# BusPirate-ultra-testboard_v1_0.net
KiCad netlist of a schematic drawn in EAGLE
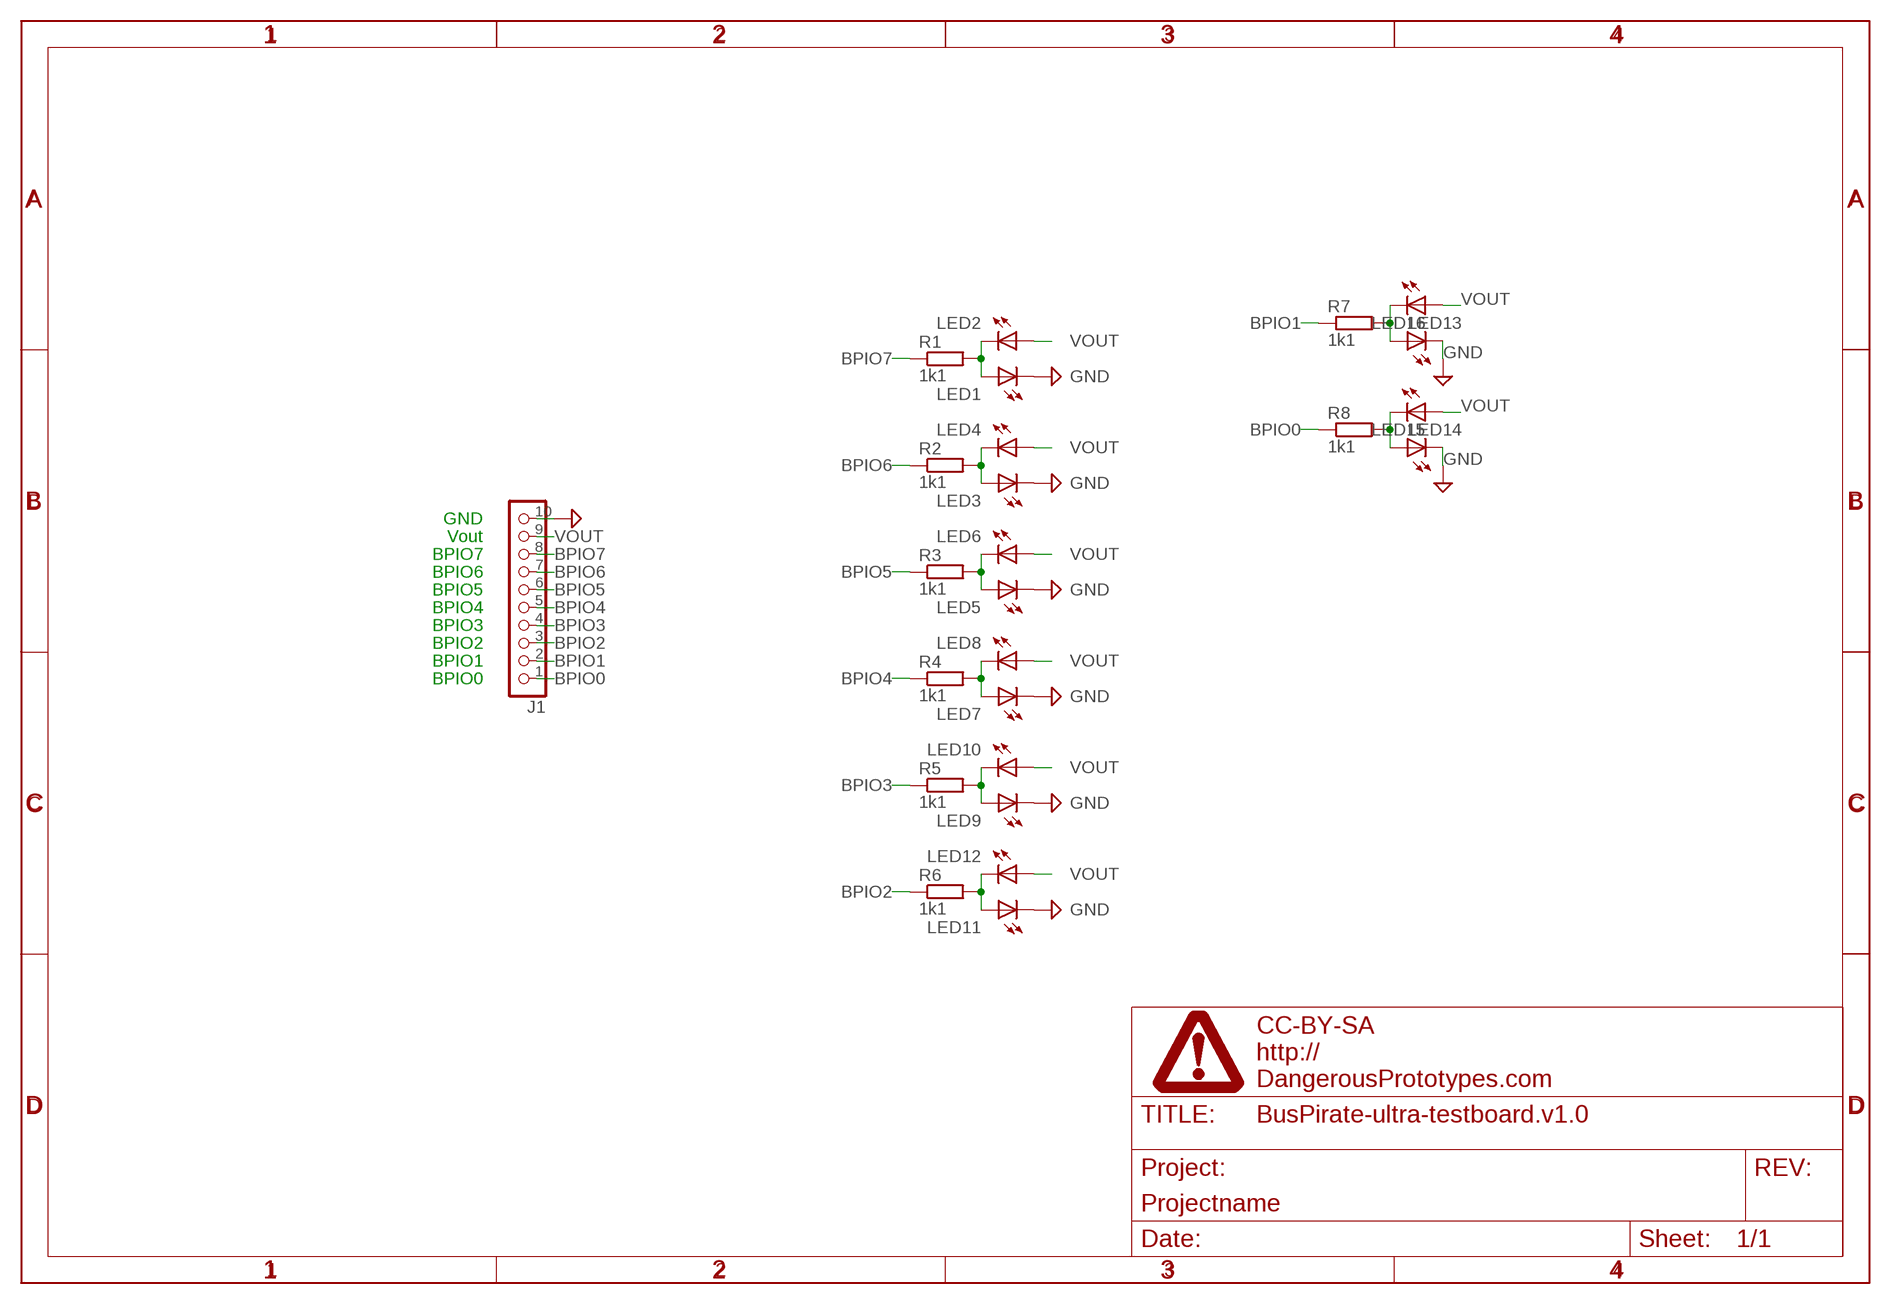
[diagram p0: schematic, sheet 1]

(export (version "E")
  (design (tool "Eeschema 10.0.6"))
  (components
    (comp (ref "J1")
      (value "CON_HEADER_1X10-RIGHT_ANGLED_PTH")
      (footprint "eagle-import:M1X10_FEMALE_RIGHT_ANGLED_PTH")
      (libsource (lib "eagle-import") (part "CON_HEADER_1X10-RIGHT_ANGLED_PTH"))
    )
    (comp (ref "LED1")
      (value "LED-0805")
      (footprint "eagle-import:LED-805")
      (libsource (lib "eagle-import") (part "LED-0805"))
    )
    (comp (ref "LED2")
      (value "LED-0805")
      (footprint "eagle-import:LED-805")
      (libsource (lib "eagle-import") (part "LED-0805"))
    )
    (comp (ref "LED3")
      (value "LED-0805")
      (footprint "eagle-import:LED-805")
      (libsource (lib "eagle-import") (part "LED-0805"))
    )
    (comp (ref "LED4")
      (value "LED-0805")
      (footprint "eagle-import:LED-805")
      (libsource (lib "eagle-import") (part "LED-0805"))
    )
    (comp (ref "LED5")
      (value "LED-0805")
      (footprint "eagle-import:LED-805")
      (libsource (lib "eagle-import") (part "LED-0805"))
    )
    (comp (ref "LED6")
      (value "LED-0805")
      (footprint "eagle-import:LED-805")
      (libsource (lib "eagle-import") (part "LED-0805"))
    )
    (comp (ref "LED7")
      (value "LED-0805")
      (footprint "eagle-import:LED-805")
      (libsource (lib "eagle-import") (part "LED-0805"))
    )
    (comp (ref "LED8")
      (value "LED-0805")
      (footprint "eagle-import:LED-805")
      (libsource (lib "eagle-import") (part "LED-0805"))
    )
    (comp (ref "LED9")
      (value "LED-0805")
      (footprint "eagle-import:LED-805")
      (libsource (lib "eagle-import") (part "LED-0805"))
    )
    (comp (ref "LED10")
      (value "LED-0805")
      (footprint "eagle-import:LED-805")
      (libsource (lib "eagle-import") (part "LED-0805"))
    )
    (comp (ref "LED11")
      (value "LED-0805")
      (footprint "eagle-import:LED-805")
      (libsource (lib "eagle-import") (part "LED-0805"))
    )
    (comp (ref "LED12")
      (value "LED-0805")
      (footprint "eagle-import:LED-805")
      (libsource (lib "eagle-import") (part "LED-0805"))
    )
    (comp (ref "LED13")
      (value "LED-0805")
      (footprint "eagle-import:LED-805")
      (libsource (lib "eagle-import") (part "LED-0805"))
    )
    (comp (ref "LED14")
      (value "LED-0805")
      (footprint "eagle-import:LED-805")
      (libsource (lib "eagle-import") (part "LED-0805"))
    )
    (comp (ref "LED15")
      (value "LED-0805")
      (footprint "eagle-import:LED-805")
      (libsource (lib "eagle-import") (part "LED-0805"))
    )
    (comp (ref "LED16")
      (value "LED-0805")
      (footprint "eagle-import:LED-805")
      (libsource (lib "eagle-import") (part "LED-0805"))
    )
    (comp (ref "PAGE1")
      (value "FRAME_DINA4_L")
      (footprint "eagle-import:DP_LOGO")
      (fields
        (field (name "LICENSE") "CC-BY-SA")
        (field (name "URL1") "http://")
        (field (name "URL2") "DangerousPrototypes.com")
        (field (name "PROJECT") "Projectname")
      )
      (libsource (lib "eagle-import") (part "FRAME_DINA4_L"))
    )
    (comp (ref "R1")
      (value "1k1")
      (footprint "eagle-import:R603")
      (libsource (lib "eagle-import") (part "RESISTOR-0603"))
    )
    (comp (ref "R2")
      (value "1k1")
      (footprint "eagle-import:R603")
      (libsource (lib "eagle-import") (part "RESISTOR-0603"))
    )
    (comp (ref "R3")
      (value "1k1")
      (footprint "eagle-import:R603")
      (libsource (lib "eagle-import") (part "RESISTOR-0603"))
    )
    (comp (ref "R4")
      (value "1k1")
      (footprint "eagle-import:R603")
      (libsource (lib "eagle-import") (part "RESISTOR-0603"))
    )
    (comp (ref "R5")
      (value "1k1")
      (footprint "eagle-import:R603")
      (libsource (lib "eagle-import") (part "RESISTOR-0603"))
    )
    (comp (ref "R6")
      (value "1k1")
      (footprint "eagle-import:R603")
      (libsource (lib "eagle-import") (part "RESISTOR-0603"))
    )
    (comp (ref "R7")
      (value "1k1")
      (footprint "eagle-import:R603")
      (libsource (lib "eagle-import") (part "RESISTOR-0603"))
    )
    (comp (ref "R8")
      (value "1k1")
      (footprint "eagle-import:R603")
      (libsource (lib "eagle-import") (part "RESISTOR-0603"))
    )
  )
  (nets
    (net (code "1") (name "/BPIO0") (class "Default")
      (node (ref "J1") (pin "1") (pinfunction "1_1") (pintype "passive"))
      (node (ref "R8") (pin "1") (pinfunction "1_1") (pintype "passive"))
    )
    (net (code "2") (name "/BPIO1") (class "Default")
      (node (ref "J1") (pin "2") (pinfunction "2_2") (pintype "passive"))
      (node (ref "R7") (pin "1") (pinfunction "1_1") (pintype "passive"))
    )
    (net (code "3") (name "/BPIO2") (class "Default")
      (node (ref "J1") (pin "3") (pinfunction "3_3") (pintype "passive"))
      (node (ref "R6") (pin "1") (pinfunction "1_1") (pintype "passive"))
    )
    (net (code "4") (name "/BPIO3") (class "Default")
      (node (ref "J1") (pin "4") (pinfunction "4_4") (pintype "passive"))
      (node (ref "R5") (pin "1") (pinfunction "1_1") (pintype "passive"))
    )
    (net (code "5") (name "/BPIO4") (class "Default")
      (node (ref "J1") (pin "5") (pinfunction "5_5") (pintype "passive"))
      (node (ref "R4") (pin "1") (pinfunction "1_1") (pintype "passive"))
    )
    (net (code "6") (name "/BPIO5") (class "Default")
      (node (ref "J1") (pin "6") (pinfunction "6_6") (pintype "passive"))
      (node (ref "R3") (pin "1") (pinfunction "1_1") (pintype "passive"))
    )
    (net (code "7") (name "/BPIO6") (class "Default")
      (node (ref "J1") (pin "7") (pinfunction "7_7") (pintype "passive"))
      (node (ref "R2") (pin "1") (pinfunction "1_1") (pintype "passive"))
    )
    (net (code "8") (name "/BPIO7") (class "Default")
      (node (ref "J1") (pin "8") (pinfunction "8_8") (pintype "passive"))
      (node (ref "R1") (pin "1") (pinfunction "1_1") (pintype "passive"))
    )
    (net (code "9") (name "/VOUT") (class "Default")
      (node (ref "J1") (pin "9") (pinfunction "9_9") (pintype "passive"))
      (node (ref "LED10") (pin "A") (pinfunction "A_A") (pintype "passive"))
      (node (ref "LED12") (pin "A") (pinfunction "A_A") (pintype "passive"))
      (node (ref "LED15") (pin "A") (pinfunction "A_A") (pintype "passive"))
      (node (ref "LED16") (pin "A") (pinfunction "A_A") (pintype "passive"))
      (node (ref "LED2") (pin "A") (pinfunction "A_A") (pintype "passive"))
      (node (ref "LED4") (pin "A") (pinfunction "A_A") (pintype "passive"))
      (node (ref "LED6") (pin "A") (pinfunction "A_A") (pintype "passive"))
      (node (ref "LED8") (pin "A") (pinfunction "A_A") (pintype "passive"))
    )
    (net (code "10") (name "DGND") (class "Default")
      (node (ref "J1") (pin "10") (pinfunction "10_10") (pintype "passive"))
      (node (ref "LED1") (pin "C") (pinfunction "C_C") (pintype "passive"))
      (node (ref "LED11") (pin "C") (pinfunction "C_C") (pintype "passive"))
      (node (ref "LED13") (pin "C") (pinfunction "C_C") (pintype "passive"))
      (node (ref "LED14") (pin "C") (pinfunction "C_C") (pintype "passive"))
      (node (ref "LED3") (pin "C") (pinfunction "C_C") (pintype "passive"))
      (node (ref "LED5") (pin "C") (pinfunction "C_C") (pintype "passive"))
      (node (ref "LED7") (pin "C") (pinfunction "C_C") (pintype "passive"))
      (node (ref "LED9") (pin "C") (pinfunction "C_C") (pintype "passive"))
    )
    (net (code "11") (name "Net-(LED1-PadA)") (class "Default")
      (node (ref "LED1") (pin "A") (pinfunction "A_A") (pintype "passive"))
      (node (ref "LED2") (pin "C") (pinfunction "C_C") (pintype "passive"))
      (node (ref "R1") (pin "2") (pinfunction "2_2") (pintype "passive"))
    )
    (net (code "12") (name "Net-(LED3-PadA)") (class "Default")
      (node (ref "LED3") (pin "A") (pinfunction "A_A") (pintype "passive"))
      (node (ref "LED4") (pin "C") (pinfunction "C_C") (pintype "passive"))
      (node (ref "R2") (pin "2") (pinfunction "2_2") (pintype "passive"))
    )
    (net (code "13") (name "Net-(LED5-PadA)") (class "Default")
      (node (ref "LED5") (pin "A") (pinfunction "A_A") (pintype "passive"))
      (node (ref "LED6") (pin "C") (pinfunction "C_C") (pintype "passive"))
      (node (ref "R3") (pin "2") (pinfunction "2_2") (pintype "passive"))
    )
    (net (code "14") (name "Net-(LED7-PadA)") (class "Default")
      (node (ref "LED7") (pin "A") (pinfunction "A_A") (pintype "passive"))
      (node (ref "LED8") (pin "C") (pinfunction "C_C") (pintype "passive"))
      (node (ref "R4") (pin "2") (pinfunction "2_2") (pintype "passive"))
    )
    (net (code "15") (name "Net-(LED10-PadC)") (class "Default")
      (node (ref "LED10") (pin "C") (pinfunction "C_C") (pintype "passive"))
      (node (ref "LED9") (pin "A") (pinfunction "A_A") (pintype "passive"))
      (node (ref "R5") (pin "2") (pinfunction "2_2") (pintype "passive"))
    )
    (net (code "16") (name "Net-(LED11-PadA)") (class "Default")
      (node (ref "LED11") (pin "A") (pinfunction "A_A") (pintype "passive"))
      (node (ref "LED12") (pin "C") (pinfunction "C_C") (pintype "passive"))
      (node (ref "R6") (pin "2") (pinfunction "2_2") (pintype "passive"))
    )
    (net (code "17") (name "Net-(LED13-PadA)") (class "Default")
      (node (ref "LED13") (pin "A") (pinfunction "A_A") (pintype "passive"))
      (node (ref "LED16") (pin "C") (pinfunction "C_C") (pintype "passive"))
      (node (ref "R7") (pin "2") (pinfunction "2_2") (pintype "passive"))
    )
    (net (code "18") (name "Net-(LED14-PadA)") (class "Default")
      (node (ref "LED14") (pin "A") (pinfunction "A_A") (pintype "passive"))
      (node (ref "LED15") (pin "C") (pinfunction "C_C") (pintype "passive"))
      (node (ref "R8") (pin "2") (pinfunction "2_2") (pintype "passive"))
    )
  )
)
